# 64_channel_Standard_Array_EIB_v1_1.net
KiCad netlist of a schematic drawn in EAGLE
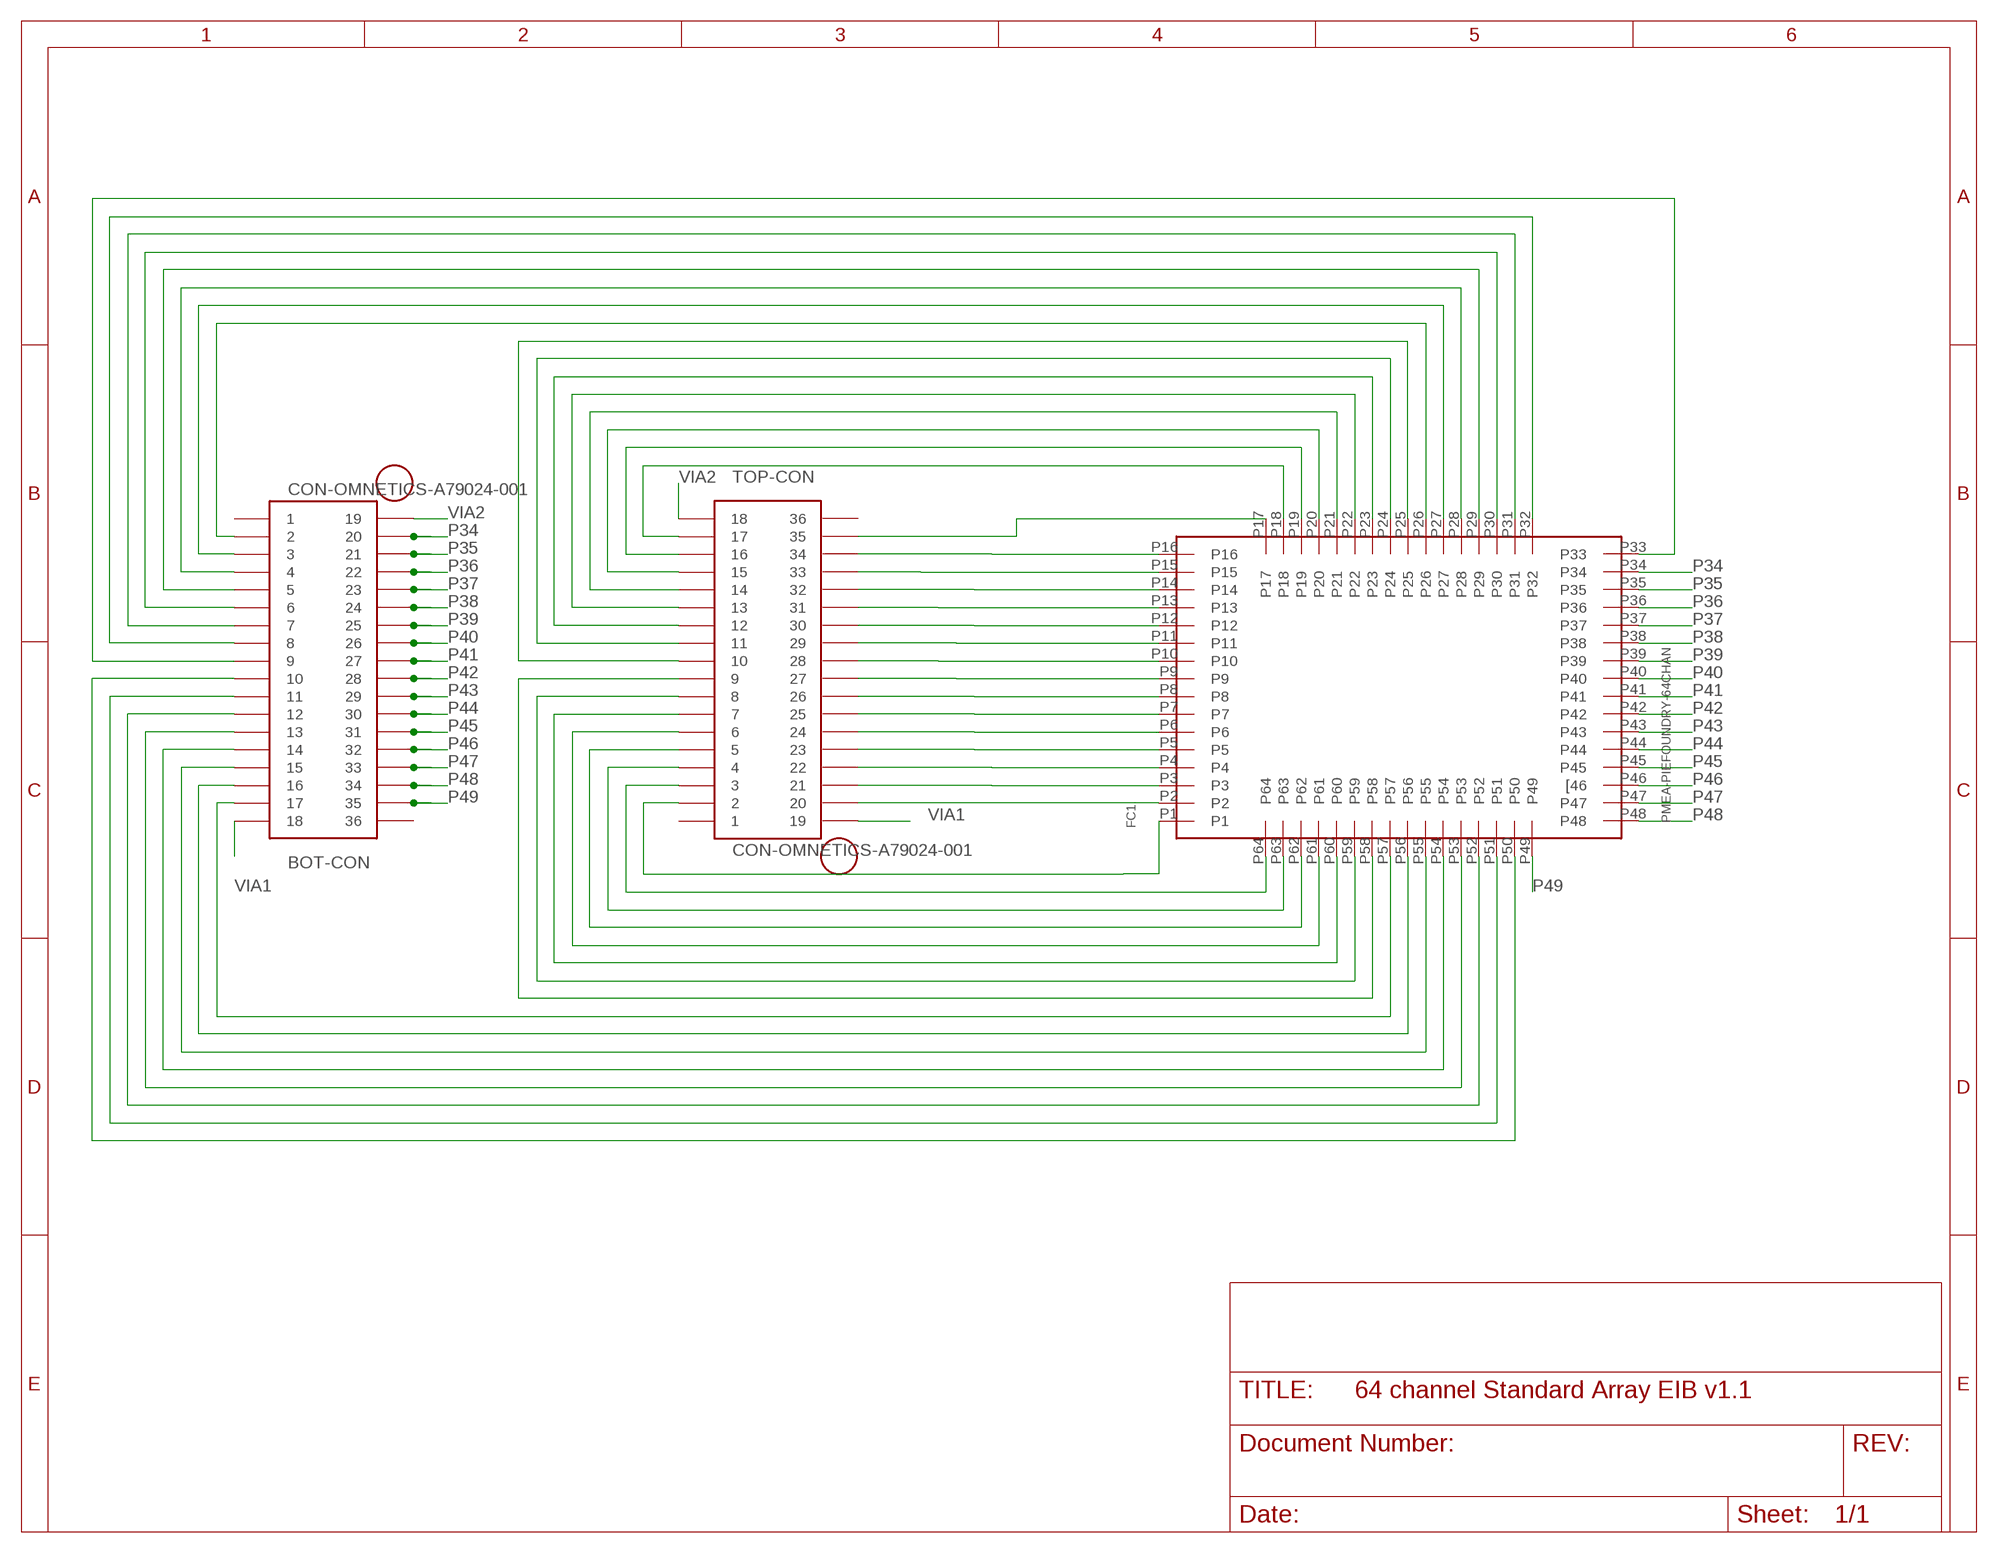
[diagram p0: schematic, sheet 1]

(export (version "E")
  (design (tool "Eeschema 10.0.6"))
  (components
    (comp (ref "BOT-CON")
      (value "CON-OMNETICS-A79024-001")
      (footprint "eagle-import:CON-OMNETICS-A79024-001")
      (libsource (lib "eagle-import") (part "CON-OMNETICS-A79024-001"))
    )
    (comp (ref "FC1")
      (value "PMEA-PIEFOUNDRY-64CHAN")
      (footprint "eagle-import:PMEA-PIEFOUNDRY-64CHAN")
      (libsource (lib "eagle-import") (part "PMEA-PIEFOUNDRY-64CHAN"))
    )
    (comp (ref "TOP-CON")
      (value "CON-OMNETICS-A79024-001")
      (footprint "eagle-import:CON-OMNETICS-A79024-001")
      (libsource (lib "eagle-import") (part "CON-OMNETICS-A79024-001"))
    )
  )
  (nets
    (net (code "1") (name "/P34") (class "Default")
      (node (ref "BOT-CON") (pin "20") (pinfunction "20_20") (pintype "bidirectional"))
      (node (ref "FC1") (pin "P34") (pinfunction "P34_P34") (pintype "bidirectional"))
    )
    (net (code "2") (name "/P35") (class "Default")
      (node (ref "BOT-CON") (pin "21") (pinfunction "21_21") (pintype "bidirectional"))
      (node (ref "FC1") (pin "P35") (pinfunction "P35_P35") (pintype "bidirectional"))
    )
    (net (code "3") (name "/P36") (class "Default")
      (node (ref "BOT-CON") (pin "22") (pinfunction "22_22") (pintype "bidirectional"))
      (node (ref "FC1") (pin "P36") (pinfunction "P36_P36") (pintype "bidirectional"))
    )
    (net (code "4") (name "/P37") (class "Default")
      (node (ref "BOT-CON") (pin "23") (pinfunction "23_23") (pintype "bidirectional"))
      (node (ref "FC1") (pin "P37") (pinfunction "P37_P37") (pintype "bidirectional"))
    )
    (net (code "5") (name "/P38") (class "Default")
      (node (ref "BOT-CON") (pin "24") (pinfunction "24_24") (pintype "bidirectional"))
      (node (ref "FC1") (pin "P38") (pinfunction "P38_P38") (pintype "bidirectional"))
    )
    (net (code "6") (name "/P39") (class "Default")
      (node (ref "BOT-CON") (pin "25") (pinfunction "25_25") (pintype "bidirectional"))
      (node (ref "FC1") (pin "P39") (pinfunction "P39_P39") (pintype "bidirectional"))
    )
    (net (code "7") (name "/P40") (class "Default")
      (node (ref "BOT-CON") (pin "26") (pinfunction "26_26") (pintype "bidirectional"))
      (node (ref "FC1") (pin "P40") (pinfunction "P40_P40") (pintype "bidirectional"))
    )
    (net (code "8") (name "/P41") (class "Default")
      (node (ref "BOT-CON") (pin "27") (pinfunction "27_27") (pintype "bidirectional"))
      (node (ref "FC1") (pin "P41") (pinfunction "P41_P41") (pintype "bidirectional"))
    )
    (net (code "9") (name "/P42") (class "Default")
      (node (ref "BOT-CON") (pin "28") (pinfunction "28_28") (pintype "bidirectional"))
      (node (ref "FC1") (pin "P42") (pinfunction "P42_P42") (pintype "bidirectional"))
    )
    (net (code "10") (name "/P43") (class "Default")
      (node (ref "BOT-CON") (pin "29") (pinfunction "29_29") (pintype "bidirectional"))
      (node (ref "FC1") (pin "P43") (pinfunction "P43_P43") (pintype "bidirectional"))
    )
    (net (code "11") (name "/P44") (class "Default")
      (node (ref "BOT-CON") (pin "30") (pinfunction "30_30") (pintype "bidirectional"))
      (node (ref "FC1") (pin "P44") (pinfunction "P44_P44") (pintype "bidirectional"))
    )
    (net (code "12") (name "/P45") (class "Default")
      (node (ref "BOT-CON") (pin "31") (pinfunction "31_31") (pintype "bidirectional"))
      (node (ref "FC1") (pin "P45") (pinfunction "P45_P45") (pintype "bidirectional"))
    )
    (net (code "13") (name "/P46") (class "Default")
      (node (ref "BOT-CON") (pin "32") (pinfunction "32_32") (pintype "bidirectional"))
      (node (ref "FC1") (pin "P46") (pinfunction "[46_P46") (pintype "bidirectional"))
    )
    (net (code "14") (name "/P47") (class "Default")
      (node (ref "BOT-CON") (pin "33") (pinfunction "33_33") (pintype "bidirectional"))
      (node (ref "FC1") (pin "P47") (pinfunction "P47_P47") (pintype "bidirectional"))
    )
    (net (code "15") (name "/P48") (class "Default")
      (node (ref "BOT-CON") (pin "34") (pinfunction "34_34") (pintype "bidirectional"))
      (node (ref "FC1") (pin "P48") (pinfunction "P48_P48") (pintype "bidirectional"))
    )
    (net (code "16") (name "/P49") (class "Default")
      (node (ref "BOT-CON") (pin "35") (pinfunction "35_35") (pintype "bidirectional"))
      (node (ref "FC1") (pin "P49") (pinfunction "P49_P49") (pintype "bidirectional"))
    )
    (net (code "17") (name "/VIA1") (class "Default")
      (node (ref "BOT-CON") (pin "18") (pinfunction "18_18") (pintype "bidirectional"))
      (node (ref "TOP-CON") (pin "19") (pinfunction "19_19") (pintype "bidirectional"))
    )
    (net (code "18") (name "/VIA2") (class "Default")
      (node (ref "BOT-CON") (pin "19") (pinfunction "19_19") (pintype "bidirectional"))
      (node (ref "TOP-CON") (pin "18") (pinfunction "18_18") (pintype "bidirectional"))
    )
    (net (code "19") (name "Net-(BOT-CON-Pad2)") (class "Default")
      (node (ref "BOT-CON") (pin "2") (pinfunction "2_2") (pintype "bidirectional"))
      (node (ref "FC1") (pin "P26") (pinfunction "P26_P26") (pintype "bidirectional"))
    )
    (net (code "20") (name "Net-(BOT-CON-Pad3)") (class "Default")
      (node (ref "BOT-CON") (pin "3") (pinfunction "3_3") (pintype "bidirectional"))
      (node (ref "FC1") (pin "P27") (pinfunction "P27_P27") (pintype "bidirectional"))
    )
    (net (code "21") (name "Net-(BOT-CON-Pad4)") (class "Default")
      (node (ref "BOT-CON") (pin "4") (pinfunction "4_4") (pintype "bidirectional"))
      (node (ref "FC1") (pin "P28") (pinfunction "P28_P28") (pintype "bidirectional"))
    )
    (net (code "22") (name "Net-(BOT-CON-Pad5)") (class "Default")
      (node (ref "BOT-CON") (pin "5") (pinfunction "5_5") (pintype "bidirectional"))
      (node (ref "FC1") (pin "P29") (pinfunction "P29_P29") (pintype "bidirectional"))
    )
    (net (code "23") (name "Net-(BOT-CON-Pad6)") (class "Default")
      (node (ref "BOT-CON") (pin "6") (pinfunction "6_6") (pintype "bidirectional"))
      (node (ref "FC1") (pin "P30") (pinfunction "P30_P30") (pintype "bidirectional"))
    )
    (net (code "24") (name "Net-(BOT-CON-Pad7)") (class "Default")
      (node (ref "BOT-CON") (pin "7") (pinfunction "7_7") (pintype "bidirectional"))
      (node (ref "FC1") (pin "P31") (pinfunction "P31_P31") (pintype "bidirectional"))
    )
    (net (code "25") (name "Net-(BOT-CON-Pad8)") (class "Default")
      (node (ref "BOT-CON") (pin "8") (pinfunction "8_8") (pintype "bidirectional"))
      (node (ref "FC1") (pin "P32") (pinfunction "P32_P32") (pintype "bidirectional"))
    )
    (net (code "26") (name "Net-(BOT-CON-Pad9)") (class "Default")
      (node (ref "BOT-CON") (pin "9") (pinfunction "9_9") (pintype "bidirectional"))
      (node (ref "FC1") (pin "P33") (pinfunction "P33_P33") (pintype "bidirectional"))
    )
    (net (code "27") (name "Net-(BOT-CON-Pad10)") (class "Default")
      (node (ref "BOT-CON") (pin "10") (pinfunction "10_10") (pintype "bidirectional"))
      (node (ref "FC1") (pin "P50") (pinfunction "P50_P50") (pintype "bidirectional"))
    )
    (net (code "28") (name "Net-(BOT-CON-Pad11)") (class "Default")
      (node (ref "BOT-CON") (pin "11") (pinfunction "11_11") (pintype "bidirectional"))
      (node (ref "FC1") (pin "P51") (pinfunction "P51_P51") (pintype "bidirectional"))
    )
    (net (code "29") (name "Net-(BOT-CON-Pad12)") (class "Default")
      (node (ref "BOT-CON") (pin "12") (pinfunction "12_12") (pintype "bidirectional"))
      (node (ref "FC1") (pin "P52") (pinfunction "P52_P52") (pintype "bidirectional"))
    )
    (net (code "30") (name "Net-(BOT-CON-Pad13)") (class "Default")
      (node (ref "BOT-CON") (pin "13") (pinfunction "13_13") (pintype "bidirectional"))
      (node (ref "FC1") (pin "P53") (pinfunction "P53_P53") (pintype "bidirectional"))
    )
    (net (code "31") (name "Net-(BOT-CON-Pad14)") (class "Default")
      (node (ref "BOT-CON") (pin "14") (pinfunction "14_14") (pintype "bidirectional"))
      (node (ref "FC1") (pin "P54") (pinfunction "P54_P54") (pintype "bidirectional"))
    )
    (net (code "32") (name "Net-(BOT-CON-Pad15)") (class "Default")
      (node (ref "BOT-CON") (pin "15") (pinfunction "15_15") (pintype "bidirectional"))
      (node (ref "FC1") (pin "P55") (pinfunction "P55_P55") (pintype "bidirectional"))
    )
    (net (code "33") (name "Net-(BOT-CON-Pad16)") (class "Default")
      (node (ref "BOT-CON") (pin "16") (pinfunction "16_16") (pintype "bidirectional"))
      (node (ref "FC1") (pin "P56") (pinfunction "P56_P56") (pintype "bidirectional"))
    )
    (net (code "34") (name "Net-(BOT-CON-Pad17)") (class "Default")
      (node (ref "BOT-CON") (pin "17") (pinfunction "17_17") (pintype "bidirectional"))
      (node (ref "FC1") (pin "P57") (pinfunction "P57_P57") (pintype "bidirectional"))
    )
    (net (code "35") (name "Net-(FC1-PadP1)") (class "Default")
      (node (ref "FC1") (pin "P1") (pinfunction "P1_P1") (pintype "bidirectional"))
      (node (ref "TOP-CON") (pin "2") (pinfunction "2_2") (pintype "bidirectional"))
    )
    (net (code "36") (name "Net-(FC1-PadP2)") (class "Default")
      (node (ref "FC1") (pin "P2") (pinfunction "P2_P2") (pintype "bidirectional"))
      (node (ref "TOP-CON") (pin "20") (pinfunction "20_20") (pintype "bidirectional"))
    )
    (net (code "37") (name "Net-(FC1-PadP3)") (class "Default")
      (node (ref "FC1") (pin "P3") (pinfunction "P3_P3") (pintype "bidirectional"))
      (node (ref "TOP-CON") (pin "21") (pinfunction "21_21") (pintype "bidirectional"))
    )
    (net (code "38") (name "Net-(FC1-PadP4)") (class "Default")
      (node (ref "FC1") (pin "P4") (pinfunction "P4_P4") (pintype "bidirectional"))
      (node (ref "TOP-CON") (pin "22") (pinfunction "22_22") (pintype "bidirectional"))
    )
    (net (code "39") (name "Net-(FC1-PadP5)") (class "Default")
      (node (ref "FC1") (pin "P5") (pinfunction "P5_P5") (pintype "bidirectional"))
      (node (ref "TOP-CON") (pin "23") (pinfunction "23_23") (pintype "bidirectional"))
    )
    (net (code "40") (name "Net-(FC1-PadP6)") (class "Default")
      (node (ref "FC1") (pin "P6") (pinfunction "P6_P6") (pintype "bidirectional"))
      (node (ref "TOP-CON") (pin "24") (pinfunction "24_24") (pintype "bidirectional"))
    )
    (net (code "41") (name "Net-(FC1-PadP7)") (class "Default")
      (node (ref "FC1") (pin "P7") (pinfunction "P7_P7") (pintype "bidirectional"))
      (node (ref "TOP-CON") (pin "25") (pinfunction "25_25") (pintype "bidirectional"))
    )
    (net (code "42") (name "Net-(FC1-PadP8)") (class "Default")
      (node (ref "FC1") (pin "P8") (pinfunction "P8_P8") (pintype "bidirectional"))
      (node (ref "TOP-CON") (pin "26") (pinfunction "26_26") (pintype "bidirectional"))
    )
    (net (code "43") (name "Net-(FC1-PadP9)") (class "Default")
      (node (ref "FC1") (pin "P9") (pinfunction "P9_P9") (pintype "bidirectional"))
      (node (ref "TOP-CON") (pin "27") (pinfunction "27_27") (pintype "bidirectional"))
    )
    (net (code "44") (name "Net-(FC1-PadP10)") (class "Default")
      (node (ref "FC1") (pin "P10") (pinfunction "P10_P10") (pintype "bidirectional"))
      (node (ref "TOP-CON") (pin "28") (pinfunction "28_28") (pintype "bidirectional"))
    )
    (net (code "45") (name "Net-(FC1-PadP11)") (class "Default")
      (node (ref "FC1") (pin "P11") (pinfunction "P11_P11") (pintype "bidirectional"))
      (node (ref "TOP-CON") (pin "29") (pinfunction "29_29") (pintype "bidirectional"))
    )
    (net (code "46") (name "Net-(FC1-PadP12)") (class "Default")
      (node (ref "FC1") (pin "P12") (pinfunction "P12_P12") (pintype "bidirectional"))
      (node (ref "TOP-CON") (pin "30") (pinfunction "30_30") (pintype "bidirectional"))
    )
    (net (code "47") (name "Net-(FC1-PadP13)") (class "Default")
      (node (ref "FC1") (pin "P13") (pinfunction "P13_P13") (pintype "bidirectional"))
      (node (ref "TOP-CON") (pin "31") (pinfunction "31_31") (pintype "bidirectional"))
    )
    (net (code "48") (name "Net-(FC1-PadP14)") (class "Default")
      (node (ref "FC1") (pin "P14") (pinfunction "P14_P14") (pintype "bidirectional"))
      (node (ref "TOP-CON") (pin "32") (pinfunction "32_32") (pintype "bidirectional"))
    )
    (net (code "49") (name "Net-(FC1-PadP15)") (class "Default")
      (node (ref "FC1") (pin "P15") (pinfunction "P15_P15") (pintype "bidirectional"))
      (node (ref "TOP-CON") (pin "33") (pinfunction "33_33") (pintype "bidirectional"))
    )
    (net (code "50") (name "Net-(FC1-PadP16)") (class "Default")
      (node (ref "FC1") (pin "P16") (pinfunction "P16_P16") (pintype "bidirectional"))
      (node (ref "TOP-CON") (pin "34") (pinfunction "34_34") (pintype "bidirectional"))
    )
    (net (code "51") (name "Net-(FC1-PadP17)") (class "Default")
      (node (ref "FC1") (pin "P17") (pinfunction "P17_P17") (pintype "bidirectional"))
      (node (ref "TOP-CON") (pin "35") (pinfunction "35_35") (pintype "bidirectional"))
    )
    (net (code "52") (name "Net-(FC1-PadP18)") (class "Default")
      (node (ref "FC1") (pin "P18") (pinfunction "P18_P18") (pintype "bidirectional"))
      (node (ref "TOP-CON") (pin "17") (pinfunction "17_17") (pintype "bidirectional"))
    )
    (net (code "53") (name "Net-(FC1-PadP19)") (class "Default")
      (node (ref "FC1") (pin "P19") (pinfunction "P19_P19") (pintype "bidirectional"))
      (node (ref "TOP-CON") (pin "16") (pinfunction "16_16") (pintype "bidirectional"))
    )
    (net (code "54") (name "Net-(FC1-PadP20)") (class "Default")
      (node (ref "FC1") (pin "P20") (pinfunction "P20_P20") (pintype "bidirectional"))
      (node (ref "TOP-CON") (pin "15") (pinfunction "15_15") (pintype "bidirectional"))
    )
    (net (code "55") (name "Net-(FC1-PadP21)") (class "Default")
      (node (ref "FC1") (pin "P21") (pinfunction "P21_P21") (pintype "bidirectional"))
      (node (ref "TOP-CON") (pin "14") (pinfunction "14_14") (pintype "bidirectional"))
    )
    (net (code "56") (name "Net-(FC1-PadP22)") (class "Default")
      (node (ref "FC1") (pin "P22") (pinfunction "P22_P22") (pintype "bidirectional"))
      (node (ref "TOP-CON") (pin "13") (pinfunction "13_13") (pintype "bidirectional"))
    )
    (net (code "57") (name "Net-(FC1-PadP23)") (class "Default")
      (node (ref "FC1") (pin "P23") (pinfunction "P23_P23") (pintype "bidirectional"))
      (node (ref "TOP-CON") (pin "12") (pinfunction "12_12") (pintype "bidirectional"))
    )
    (net (code "58") (name "Net-(FC1-PadP24)") (class "Default")
      (node (ref "FC1") (pin "P24") (pinfunction "P24_P24") (pintype "bidirectional"))
      (node (ref "TOP-CON") (pin "11") (pinfunction "11_11") (pintype "bidirectional"))
    )
    (net (code "59") (name "Net-(FC1-PadP25)") (class "Default")
      (node (ref "FC1") (pin "P25") (pinfunction "P25_P25") (pintype "bidirectional"))
      (node (ref "TOP-CON") (pin "10") (pinfunction "10_10") (pintype "bidirectional"))
    )
    (net (code "60") (name "Net-(FC1-PadP58)") (class "Default")
      (node (ref "FC1") (pin "P58") (pinfunction "P58_P58") (pintype "bidirectional"))
      (node (ref "TOP-CON") (pin "9") (pinfunction "9_9") (pintype "bidirectional"))
    )
    (net (code "61") (name "Net-(FC1-PadP59)") (class "Default")
      (node (ref "FC1") (pin "P59") (pinfunction "P59_P59") (pintype "bidirectional"))
      (node (ref "TOP-CON") (pin "8") (pinfunction "8_8") (pintype "bidirectional"))
    )
    (net (code "62") (name "Net-(FC1-PadP60)") (class "Default")
      (node (ref "FC1") (pin "P60") (pinfunction "P60_P60") (pintype "bidirectional"))
      (node (ref "TOP-CON") (pin "7") (pinfunction "7_7") (pintype "bidirectional"))
    )
    (net (code "63") (name "Net-(FC1-PadP61)") (class "Default")
      (node (ref "FC1") (pin "P61") (pinfunction "P61_P61") (pintype "bidirectional"))
      (node (ref "TOP-CON") (pin "6") (pinfunction "6_6") (pintype "bidirectional"))
    )
    (net (code "64") (name "Net-(FC1-PadP62)") (class "Default")
      (node (ref "FC1") (pin "P62") (pinfunction "P62_P62") (pintype "bidirectional"))
      (node (ref "TOP-CON") (pin "5") (pinfunction "5_5") (pintype "bidirectional"))
    )
    (net (code "65") (name "Net-(FC1-PadP63)") (class "Default")
      (node (ref "FC1") (pin "P63") (pinfunction "P63_P63") (pintype "bidirectional"))
      (node (ref "TOP-CON") (pin "4") (pinfunction "4_4") (pintype "bidirectional"))
    )
    (net (code "66") (name "Net-(FC1-PadP64)") (class "Default")
      (node (ref "FC1") (pin "P64") (pinfunction "P64_P64") (pintype "bidirectional"))
      (node (ref "TOP-CON") (pin "3") (pinfunction "3_3") (pintype "bidirectional"))
    )
    (net (code "67") (name "unconnected-(BOT-CON-Pad1)") (class "Default")
      (node (ref "BOT-CON") (pin "1") (pinfunction "1_1") (pintype "bidirectional"))
    )
    (net (code "68") (name "unconnected-(BOT-CON-Pad36)") (class "Default")
      (node (ref "BOT-CON") (pin "36") (pinfunction "36_36") (pintype "bidirectional"))
    )
    (net (code "69") (name "unconnected-(TOP-CON-Pad1)") (class "Default")
      (node (ref "TOP-CON") (pin "1") (pinfunction "1_1") (pintype "bidirectional"))
    )
    (net (code "70") (name "unconnected-(TOP-CON-Pad36)") (class "Default")
      (node (ref "TOP-CON") (pin "36") (pinfunction "36_36") (pintype "bidirectional"))
    )
  )
)
